# 2211B_SysArrosageAuto_MCU.net
KiCad netlist of a schematic drawn in Altium Designer
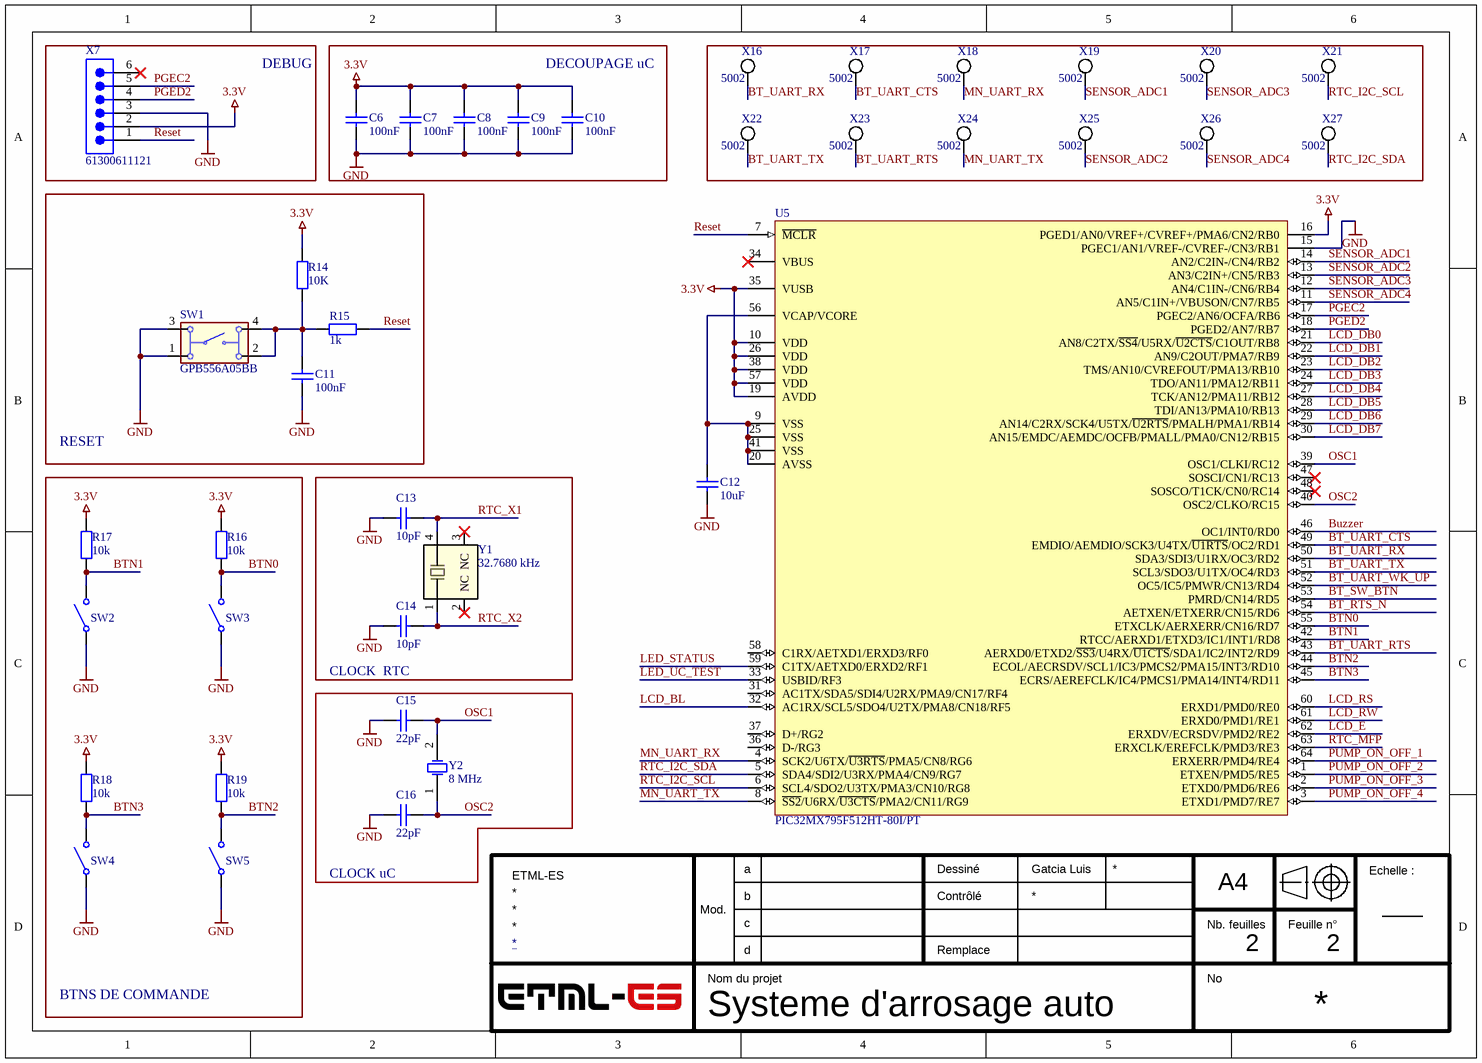
[diagram p0: 2211B_SysArrosageAuto_MCU.SchDoc]

(export (version "E")
  (design (tool "Eeschema 10.0.6"))
  (components
    (comp (ref "C6")
      (value "100nF")
      (footprint "CAPC2013X145X48NL20T23")
      (libsource (lib "Sys_Arossage") (part "Capacitor_Non-Polarized"))
    )
    (comp (ref "C7")
      (value "100nF")
      (footprint "CAPC2013X145X48NL20T23")
      (libsource (lib "Sys_Arossage") (part "Capacitor_Non-Polarized"))
    )
    (comp (ref "C8")
      (value "100nF")
      (footprint "CAPC2013X145X48NL20T23")
      (libsource (lib "Sys_Arossage") (part "Capacitor_Non-Polarized"))
    )
    (comp (ref "C9")
      (value "100nF")
      (footprint "CAPC2013X145X48NL20T23")
      (libsource (lib "Sys_Arossage") (part "Capacitor_Non-Polarized"))
    )
    (comp (ref "C10")
      (value "100nF")
      (footprint "CAPC2013X145X48NL20T23")
      (libsource (lib "Sys_Arossage") (part "Capacitor_Non-Polarized"))
    )
    (comp (ref "C11")
      (value "100nF")
      (footprint "CAPC2013X145X48NL20T23")
      (libsource (lib "Sys_Arossage") (part "Capacitor_Non-Polarized"))
    )
    (comp (ref "C12")
      (value "10uF")
      (footprint "CAPC2013X145X48NL20T23")
      (libsource (lib "Sys_Arossage") (part "Capacitor_Non-Polarized"))
    )
    (comp (ref "C13")
      (value "10pF")
      (footprint "CAPC2013X145X48NL20T23")
      (libsource (lib "Sys_Arossage") (part "Capacitor_Non-Polarized"))
    )
    (comp (ref "C14")
      (value "10pF")
      (footprint "CAPC2013X145X48NL20T23")
      (libsource (lib "Sys_Arossage") (part "Capacitor_Non-Polarized"))
    )
    (comp (ref "C15")
      (value "22pF")
      (footprint "CAPC2013X145X48NL20T23")
      (libsource (lib "Sys_Arossage") (part "Capacitor_Non-Polarized"))
    )
    (comp (ref "C16")
      (value "22pF")
      (footprint "CAPC2013X145X48NL20T23")
      (libsource (lib "Sys_Arossage") (part "Capacitor_Non-Polarized"))
    )
    (comp (ref "R14")
      (value "10K")
      (footprint "RC0805N_YAG-M")
      (description "SMD Chip Resistor, 10 kOhm, ± 1%, 125 mW, 0805 [2012 Metric], Thick Film, General Purpose")
      (fields
        (field (name "MANUFACTURER") "Yageo")
        (field (name "MANUFACTURER PART NUMBER") "RC0805FR-0710KL")
      )
      (libsource (lib "Sys_Arossage") (part "R-SMD"))
    )
    (comp (ref "R15")
      (value "1k")
      (footprint "RC0805N_YAG-M")
      (description "SMD Chip Resistor, 10 kOhm, ± 1%, 125 mW, 0805 [2012 Metric], Thick Film, General Purpose")
      (fields
        (field (name "MANUFACTURER") "Yageo")
        (field (name "MANUFACTURER PART NUMBER") "RC0805FR-0710KL")
      )
      (libsource (lib "") (part "R-SMD_1"))
    )
    (comp (ref "R16")
      (value "10k")
      (footprint "RC0805N_YAG-M")
      (description "SMD Chip Resistor, 10 kOhm, ± 1%, 125 mW, 0805 [2012 Metric], Thick Film, General Purpose")
      (fields
        (field (name "MANUFACTURER") "Yageo")
        (field (name "MANUFACTURER PART NUMBER") "RC0805FR-0710KL")
      )
      (libsource (lib "Sys_Arossage") (part "R-SMD"))
    )
    (comp (ref "R17")
      (value "10k")
      (footprint "RC0805N_YAG-M")
      (description "SMD Chip Resistor, 10 kOhm, ± 1%, 125 mW, 0805 [2012 Metric], Thick Film, General Purpose")
      (fields
        (field (name "MANUFACTURER") "Yageo")
        (field (name "MANUFACTURER PART NUMBER") "RC0805FR-0710KL")
      )
      (libsource (lib "Sys_Arossage") (part "R-SMD"))
    )
    (comp (ref "R18")
      (value "10k")
      (footprint "RC0805N_YAG-M")
      (description "SMD Chip Resistor, 10 kOhm, ± 1%, 125 mW, 0805 [2012 Metric], Thick Film, General Purpose")
      (fields
        (field (name "MANUFACTURER") "Yageo")
        (field (name "MANUFACTURER PART NUMBER") "RC0805FR-0710KL")
      )
      (libsource (lib "Sys_Arossage") (part "R-SMD"))
    )
    (comp (ref "R19")
      (value "10k")
      (footprint "RC0805N_YAG-M")
      (description "SMD Chip Resistor, 10 kOhm, ± 1%, 125 mW, 0805 [2012 Metric], Thick Film, General Purpose")
      (fields
        (field (name "MANUFACTURER") "Yageo")
        (field (name "MANUFACTURER PART NUMBER") "RC0805FR-0710KL")
      )
      (libsource (lib "Sys_Arossage") (part "R-SMD"))
    )
    (comp (ref "SW1") (value "GPB556A05BB") (libsource (lib "Sys_Arossage") (part "SWITCH_SPST-NO")))
    (comp (ref "SW2")
      (value "Single-Pole,Single-Throw Switch")
      (footprint "FP-RP8100B2M1CEBLKBLKNIL-MFG")
      (libsource (lib "Sys_Arossage") (part "SPST SW"))
    )
    (comp (ref "SW3")
      (value "Single-Pole,Single-Throw Switch")
      (footprint "FP-RP8100B2M1CEBLKBLKNIL-MFG")
      (libsource (lib "Sys_Arossage") (part "SPST SW"))
    )
    (comp (ref "SW4")
      (value "Single-Pole,Single-Throw Switch")
      (footprint "FP-RP8100B2M1CEBLKBLKNIL-MFG")
      (libsource (lib "Sys_Arossage") (part "SPST SW"))
    )
    (comp (ref "SW5")
      (value "Single-Pole,Single-Throw Switch")
      (footprint "FP-RP8100B2M1CEBLKBLKNIL-MFG")
      (libsource (lib "Sys_Arossage") (part "SPST SW"))
    )
    (comp (ref "U5")
      (value "PIC32MX795F512HT-80I/PT")
      (footprint "TQFP-PT64_L")
      (libsource (lib "Sys_Arossage") (part "CMP-0048-00048-2"))
    )
    (comp (ref "X7")
      (value "61300611121")
      (footprint "61300611121")
      (description "THT Vertical Pin Header WR-PHD, Pitch 2.54 mm, Single Row, 6 pins")
      (fields (field (name "MANUFACTURER") "Wurth Electronics"))
      (libsource (lib "Sys_Arossage") (part "CMP-1502-01068-2_1"))
    )
    (comp (ref "X16")
      (value "5002")
      (footprint "Keystone_5002")
      (description "TEST THT MINIATURE WT")
      (fields (field (name "MANUFACTURER") "Keystone"))
      (libsource (lib "ETML-ES") (part "TEST"))
    )
    (comp (ref "X17")
      (value "5002")
      (footprint "Keystone_5002")
      (description "TEST THT MINIATURE WT")
      (fields (field (name "MANUFACTURER") "Keystone"))
      (libsource (lib "ETML-ES") (part "TEST"))
    )
    (comp (ref "X18")
      (value "5002")
      (footprint "Keystone_5002")
      (description "TEST THT MINIATURE WT")
      (fields (field (name "MANUFACTURER") "Keystone"))
      (libsource (lib "ETML-ES") (part "TEST"))
    )
    (comp (ref "X19")
      (value "5002")
      (footprint "Keystone_5002")
      (description "TEST THT MINIATURE WT")
      (fields (field (name "MANUFACTURER") "Keystone"))
      (libsource (lib "ETML-ES") (part "TEST"))
    )
    (comp (ref "X20")
      (value "5002")
      (footprint "Keystone_5002")
      (description "TEST THT MINIATURE WT")
      (fields (field (name "MANUFACTURER") "Keystone"))
      (libsource (lib "ETML-ES") (part "TEST"))
    )
    (comp (ref "X21")
      (value "5002")
      (footprint "Keystone_5002")
      (description "TEST THT MINIATURE WT")
      (fields (field (name "MANUFACTURER") "Keystone"))
      (libsource (lib "ETML-ES") (part "TEST"))
    )
    (comp (ref "X22")
      (value "5002")
      (footprint "Keystone_5002")
      (description "TEST THT MINIATURE WT")
      (fields (field (name "MANUFACTURER") "Keystone"))
      (libsource (lib "ETML-ES") (part "TEST"))
    )
    (comp (ref "X23")
      (value "5002")
      (footprint "Keystone_5002")
      (description "TEST THT MINIATURE WT")
      (fields (field (name "MANUFACTURER") "Keystone"))
      (libsource (lib "ETML-ES") (part "TEST"))
    )
    (comp (ref "X24")
      (value "5002")
      (footprint "Keystone_5002")
      (description "TEST THT MINIATURE WT")
      (fields (field (name "MANUFACTURER") "Keystone"))
      (libsource (lib "ETML-ES") (part "TEST"))
    )
    (comp (ref "X25")
      (value "5002")
      (footprint "Keystone_5002")
      (description "TEST THT MINIATURE WT")
      (fields (field (name "MANUFACTURER") "Keystone"))
      (libsource (lib "ETML-ES") (part "TEST"))
    )
    (comp (ref "X26")
      (value "5002")
      (footprint "Keystone_5002")
      (description "TEST THT MINIATURE WT")
      (fields (field (name "MANUFACTURER") "Keystone"))
      (libsource (lib "ETML-ES") (part "TEST"))
    )
    (comp (ref "X27")
      (value "5002")
      (footprint "Keystone_5002")
      (description "TEST THT MINIATURE WT")
      (fields (field (name "MANUFACTURER") "Keystone"))
      (libsource (lib "ETML-ES") (part "TEST"))
    )
    (comp (ref "Y1")
      (value "32.7680 kHz")
      (footprint "SOJ_MC-306_EPS-M")
      (description "CRYSTAL 32.7680KHZ 12.5PF SMD")
      (fields
        (field (name "MANUFACTURER_PART_NUMBER") "MC-306 32.7680K-A3: ROHS")
        (field (name "MANUFACTURER") "Epson")
        (field (name "COPYRIGHT") "Copyright (C) 2024 Ultra Librarian. All rights reserved.")
      )
      (libsource (lib "Sys_Arossage") (part "MC-306 32.7680K-A3{colon} ROHS"))
    )
    (comp (ref "Y2")
      (value "8 MHz")
      (description "Crystal 8MHz ±30ppm (Tol) ±50ppm (Stability) 18pF FUND 60Ohm 2-Pin HC-49/US SM SMD T/R")
      (fields
        (field (name "MANUFACTURER") "CTS")
        (field (name "MANUFACTURER PART NUMBER") "ATS080BSM-1")
        (field (name "PUBLISHER") "Altium Limited")
      )
      (libsource (lib "Sys_Arossage") (part "XTAL"))
    )
  )
  (nets
    (net (code "1") (name "/BTN0") (class "Default")
      (node (ref "R16") (pin "1") (pinfunction "1_1") (pintype "passive"))
      (node (ref "SW3") (pin "2") (pinfunction "2_2") (pintype "passive"))
      (node (ref "U5") (pin "55") (pinfunction "ETXCLK/AERXERR/CN16/RD7_55") (pintype "bidirectional"))
    )
    (net (code "2") (name "/BTN1") (class "Default")
      (node (ref "R17") (pin "1") (pinfunction "1_1") (pintype "passive"))
      (node (ref "SW2") (pin "2") (pinfunction "2_2") (pintype "passive"))
      (node (ref "U5") (pin "42") (pinfunction "RTCC/AERXD1/ETXD3/IC1/INT1/RD8_42") (pintype "bidirectional"))
    )
    (net (code "3") (name "/BTN2") (class "Default")
      (node (ref "R19") (pin "1") (pinfunction "1_1") (pintype "passive"))
      (node (ref "SW5") (pin "2") (pinfunction "2_2") (pintype "passive"))
      (node (ref "U5") (pin "44") (pinfunction "ECOL/AECRSDV/SCL1/IC3/PMCS2/PMA15/INT3/RD10_44") (pintype "bidirectional"))
    )
    (net (code "4") (name "/BTN3") (class "Default")
      (node (ref "R18") (pin "1") (pinfunction "1_1") (pintype "passive"))
      (node (ref "SW4") (pin "2") (pinfunction "2_2") (pintype "passive"))
      (node (ref "U5") (pin "45") (pinfunction "ECRS/AEREFCLK/IC4/PMCS1/PMA14/INT4/RD11_45") (pintype "bidirectional"))
    )
    (net (code "5") (name "/BT_RTS_N") (class "Default")
      (node (ref "U5") (pin "54") (pinfunction "AETXEN/ETXERR/CN15/RD6_54") (pintype "bidirectional"))
    )
    (net (code "6") (name "/BT_SW_BTN") (class "Default")
      (node (ref "U5") (pin "53") (pinfunction "PMRD/CN14/RD5_53") (pintype "bidirectional"))
    )
    (net (code "7") (name "/BT_UART_CTS") (class "Default")
      (node (ref "U5") (pin "49") (pinfunction "EMDIO/AEMDIO/SCK3/U4TX/~{U1RTS}/OC2/RD1_49") (pintype "bidirectional"))
      (node (ref "X17") (pin "1") (pinfunction "TP_1") (pintype "passive"))
    )
    (net (code "8") (name "/BT_UART_RTS") (class "Default")
      (node (ref "U5") (pin "43") (pinfunction "AERXD0/ETXD2/~{SS3}/U4RX/~{U1CTS}/SDA1/IC2/INT2/RD9_43") (pintype "bidirectional"))
      (node (ref "X23") (pin "1") (pinfunction "TP_1") (pintype "passive"))
    )
    (net (code "9") (name "/BT_UART_RX") (class "Default")
      (node (ref "U5") (pin "50") (pinfunction "SDA3/SDI3/U1RX/OC3/RD2_50") (pintype "bidirectional"))
      (node (ref "X16") (pin "1") (pinfunction "TP_1") (pintype "passive"))
    )
    (net (code "10") (name "/BT_UART_TX") (class "Default")
      (node (ref "U5") (pin "51") (pinfunction "SCL3/SDO3/U1TX/OC4/RD3_51") (pintype "bidirectional"))
      (node (ref "X22") (pin "1") (pinfunction "TP_1") (pintype "passive"))
    )
    (net (code "11") (name "/BT_UART_WK_UP") (class "Default")
      (node (ref "U5") (pin "52") (pinfunction "OC5/IC5/PMWR/CN13/RD4_52") (pintype "bidirectional"))
    )
    (net (code "12") (name "/Buzzer") (class "Default")
      (node (ref "U5") (pin "46") (pinfunction "OC1/INT0/RD0_46") (pintype "bidirectional"))
    )
    (net (code "13") (name "/LCD_BL") (class "Default")
      (node (ref "U5") (pin "32") (pinfunction "AC1RX/SCL5/SDO4/U2TX/PMA8/CN18/RF5_32") (pintype "bidirectional"))
    )
    (net (code "14") (name "/LCD_DB0") (class "Default")
      (node (ref "U5") (pin "21") (pinfunction "AN8/C2TX/~{SS4}/U5RX/~{U2CTS}/C1OUT/RB8_21") (pintype "bidirectional"))
    )
    (net (code "15") (name "/LCD_DB1") (class "Default")
      (node (ref "U5") (pin "22") (pinfunction "AN9/C2OUT/PMA7/RB9_22") (pintype "bidirectional"))
    )
    (net (code "16") (name "/LCD_DB2") (class "Default")
      (node (ref "U5") (pin "23") (pinfunction "TMS/AN10/CVREFOUT/PMA13/RB10_23") (pintype "bidirectional"))
    )
    (net (code "17") (name "/LCD_DB3") (class "Default")
      (node (ref "U5") (pin "24") (pinfunction "TDO/AN11/PMA12/RB11_24") (pintype "bidirectional"))
    )
    (net (code "18") (name "/LCD_DB4") (class "Default")
      (node (ref "U5") (pin "27") (pinfunction "TCK/AN12/PMA11/RB12_27") (pintype "bidirectional"))
    )
    (net (code "19") (name "/LCD_DB5") (class "Default")
      (node (ref "U5") (pin "28") (pinfunction "TDI/AN13/PMA10/RB13_28") (pintype "bidirectional"))
    )
    (net (code "20") (name "/LCD_DB6") (class "Default")
      (node (ref "U5") (pin "29") (pinfunction "AN14/C2RX/SCK4/U5TX/~{U2RTS}/PMALH/PMA1/RB14_29") (pintype "bidirectional"))
    )
    (net (code "21") (name "/LCD_DB7") (class "Default")
      (node (ref "U5") (pin "30") (pinfunction "AN15/EMDC/AEMDC/OCFB/PMALL/PMA0/CN12/RB15_30") (pintype "bidirectional"))
    )
    (net (code "22") (name "/LCD_E") (class "Default")
      (node (ref "U5") (pin "62") (pinfunction "ERXDV/ECRSDV/PMD2/RE2_62") (pintype "bidirectional"))
    )
    (net (code "23") (name "/LCD_RS") (class "Default")
      (node (ref "U5") (pin "60") (pinfunction "ERXD1/PMD0/RE0_60") (pintype "bidirectional"))
    )
    (net (code "24") (name "/LCD_RW") (class "Default")
      (node (ref "U5") (pin "61") (pinfunction "ERXD0/PMD1/RE1_61") (pintype "bidirectional"))
    )
    (net (code "25") (name "/LED_STATUS") (class "Default")
      (node (ref "U5") (pin "59") (pinfunction "C1TX/AETXD0/ERXD2/RF1_59") (pintype "bidirectional"))
    )
    (net (code "26") (name "/LED_UC_TEST") (class "Default")
      (node (ref "U5") (pin "33") (pinfunction "USBID/RF3_33") (pintype "bidirectional"))
    )
    (net (code "27") (name "/MN_UART_RX") (class "Default")
      (node (ref "U5") (pin "4") (pinfunction "SCK2/U6TX/~{U3RTS}/PMA5/CN8/RG6_4") (pintype "bidirectional"))
      (node (ref "X18") (pin "1") (pinfunction "TP_1") (pintype "passive"))
    )
    (net (code "28") (name "/MN_UART_TX") (class "Default")
      (node (ref "U5") (pin "8") (pinfunction "~{SS2}/U6RX/~{U3CTS}/PMA2/CN11/RG9_8") (pintype "bidirectional"))
      (node (ref "X24") (pin "1") (pinfunction "TP_1") (pintype "passive"))
    )
    (net (code "29") (name "/OSC1") (class "Default")
      (node (ref "C15") (pin "2") (pinfunction "2_2") (pintype "passive"))
      (node (ref "U5") (pin "39") (pinfunction "OSC1/CLKI/RC12_39") (pintype "bidirectional"))
      (node (ref "Y2") (pin "2") (pinfunction "OSC2_2") (pintype "passive"))
    )
    (net (code "30") (name "/OSC2") (class "Default")
      (node (ref "C16") (pin "2") (pinfunction "2_2") (pintype "passive"))
      (node (ref "U5") (pin "40") (pinfunction "OSC2/CLKO/RC15_40") (pintype "bidirectional"))
      (node (ref "Y2") (pin "1") (pinfunction "OSC1_1") (pintype "passive"))
    )
    (net (code "31") (name "/PGEC2") (class "Default")
      (node (ref "U5") (pin "17") (pinfunction "PGEC2/AN6/OCFA/RB6_17") (pintype "bidirectional"))
      (node (ref "X7") (pin "5") (pinfunction "5_5") (pintype "passive"))
    )
    (net (code "32") (name "/PGED2") (class "Default")
      (node (ref "U5") (pin "18") (pinfunction "PGED2/AN7/RB7_18") (pintype "bidirectional"))
      (node (ref "X7") (pin "4") (pinfunction "4_4") (pintype "passive"))
    )
    (net (code "33") (name "/PUMP_ON_OFF_1") (class "Default")
      (node (ref "U5") (pin "64") (pinfunction "ERXERR/PMD4/RE4_64") (pintype "bidirectional"))
    )
    (net (code "34") (name "/PUMP_ON_OFF_2") (class "Default")
      (node (ref "U5") (pin "1") (pinfunction "ETXEN/PMD5/RE5_1") (pintype "bidirectional"))
    )
    (net (code "35") (name "/PUMP_ON_OFF_3") (class "Default")
      (node (ref "U5") (pin "2") (pinfunction "ETXD0/PMD6/RE6_2") (pintype "bidirectional"))
    )
    (net (code "36") (name "/PUMP_ON_OFF_4") (class "Default")
      (node (ref "U5") (pin "3") (pinfunction "ETXD1/PMD7/RE7_3") (pintype "bidirectional"))
    )
    (net (code "37") (name "/RTC_I2C_SCL") (class "Default")
      (node (ref "U5") (pin "6") (pinfunction "SCL4/SDO2/U3TX/PMA3/CN10/RG8_6") (pintype "bidirectional"))
      (node (ref "X21") (pin "1") (pinfunction "TP_1") (pintype "passive"))
    )
    (net (code "38") (name "/RTC_I2C_SDA") (class "Default")
      (node (ref "U5") (pin "5") (pinfunction "SDA4/SDI2/U3RX/PMA4/CN9/RG7_5") (pintype "bidirectional"))
      (node (ref "X27") (pin "1") (pinfunction "TP_1") (pintype "passive"))
    )
    (net (code "39") (name "/RTC_MFP") (class "Default")
      (node (ref "U5") (pin "63") (pinfunction "ERXCLK/EREFCLK/PMD3/RE3_63") (pintype "bidirectional"))
    )
    (net (code "40") (name "/RTC_X1") (class "Default")
      (node (ref "C13") (pin "2") (pinfunction "2_2") (pintype "passive"))
      (node (ref "Y1") (pin "4") (pinfunction "4_4") (pintype "passive"))
    )
    (net (code "41") (name "/RTC_X2") (class "Default")
      (node (ref "C14") (pin "2") (pinfunction "2_2") (pintype "passive"))
      (node (ref "Y1") (pin "1") (pinfunction "1_1") (pintype "passive"))
    )
    (net (code "42") (name "/Reset") (class "Default")
      (node (ref "R15") (pin "2") (pinfunction "2_2") (pintype "passive"))
      (node (ref "U5") (pin "7") (pinfunction "~{MCLR}_7") (pintype "input"))
      (node (ref "X7") (pin "1") (pinfunction "1_1") (pintype "passive"))
    )
    (net (code "43") (name "/SENSOR_ADC1") (class "Default")
      (node (ref "U5") (pin "14") (pinfunction "AN2/C2IN-/CN4/RB2_14") (pintype "bidirectional"))
      (node (ref "X19") (pin "1") (pinfunction "TP_1") (pintype "passive"))
    )
    (net (code "44") (name "/SENSOR_ADC2") (class "Default")
      (node (ref "U5") (pin "13") (pinfunction "AN3/C2IN+/CN5/RB3_13") (pintype "bidirectional"))
      (node (ref "X25") (pin "1") (pinfunction "TP_1") (pintype "passive"))
    )
    (net (code "45") (name "/SENSOR_ADC3") (class "Default")
      (node (ref "U5") (pin "12") (pinfunction "AN4/C1IN-/CN6/RB4_12") (pintype "bidirectional"))
      (node (ref "X20") (pin "1") (pinfunction "TP_1") (pintype "passive"))
    )
    (net (code "46") (name "/SENSOR_ADC4") (class "Default")
      (node (ref "U5") (pin "11") (pinfunction "AN5/C1IN+/VBUSON/CN7/RB5_11") (pintype "bidirectional"))
      (node (ref "X26") (pin "1") (pinfunction "TP_1") (pintype "passive"))
    )
    (net (code "47") (name "3.3V") (class "Default")
      (node (ref "C10") (pin "2") (pinfunction "2_2") (pintype "passive"))
      (node (ref "C6") (pin "2") (pinfunction "2_2") (pintype "passive"))
      (node (ref "C7") (pin "2") (pinfunction "2_2") (pintype "passive"))
      (node (ref "C8") (pin "2") (pinfunction "2_2") (pintype "passive"))
      (node (ref "C9") (pin "2") (pinfunction "2_2") (pintype "passive"))
      (node (ref "R14") (pin "2") (pinfunction "2_2") (pintype "passive"))
      (node (ref "R16") (pin "2") (pinfunction "2_2") (pintype "passive"))
      (node (ref "R17") (pin "2") (pinfunction "2_2") (pintype "passive"))
      (node (ref "R18") (pin "2") (pinfunction "2_2") (pintype "passive"))
      (node (ref "R19") (pin "2") (pinfunction "2_2") (pintype "passive"))
      (node (ref "U5") (pin "10") (pinfunction "VDD_10") (pintype "passive"))
      (node (ref "U5") (pin "16") (pinfunction "PGED1/AN0/VREF+/CVREF+/PMA6/CN2/RB0_16") (pintype "power_in"))
      (node (ref "U5") (pin "19") (pinfunction "AVDD_19") (pintype "passive"))
      (node (ref "U5") (pin "26") (pinfunction "VDD_26") (pintype "passive"))
      (node (ref "U5") (pin "35") (pinfunction "VUSB_35") (pintype "passive"))
      (node (ref "U5") (pin "38") (pinfunction "VDD_38") (pintype "passive"))
      (node (ref "U5") (pin "57") (pinfunction "VDD_57") (pintype "passive"))
      (node (ref "X7") (pin "2") (pinfunction "2_2") (pintype "passive"))
    )
    (net (code "48") (name "GND") (class "Default")
      (node (ref "C10") (pin "1") (pinfunction "1_1") (pintype "passive"))
      (node (ref "C11") (pin "1") (pinfunction "1_1") (pintype "passive"))
      (node (ref "C12") (pin "1") (pinfunction "1_1") (pintype "passive"))
      (node (ref "C13") (pin "1") (pinfunction "1_1") (pintype "passive"))
      (node (ref "C14") (pin "1") (pinfunction "1_1") (pintype "passive"))
      (node (ref "C15") (pin "1") (pinfunction "1_1") (pintype "passive"))
      (node (ref "C16") (pin "1") (pinfunction "1_1") (pintype "passive"))
      (node (ref "C6") (pin "1") (pinfunction "1_1") (pintype "passive"))
      (node (ref "C7") (pin "1") (pinfunction "1_1") (pintype "passive"))
      (node (ref "C8") (pin "1") (pinfunction "1_1") (pintype "passive"))
      (node (ref "C9") (pin "1") (pinfunction "1_1") (pintype "passive"))
      (node (ref "SW1") (pin "1") (pinfunction "1_1") (pintype "passive"))
      (node (ref "SW1") (pin "3") (pinfunction "3_3") (pintype "passive"))
      (node (ref "SW2") (pin "1") (pinfunction "1_1") (pintype "passive"))
      (node (ref "SW3") (pin "1") (pinfunction "1_1") (pintype "passive"))
      (node (ref "SW4") (pin "1") (pinfunction "1_1") (pintype "passive"))
      (node (ref "SW5") (pin "1") (pinfunction "1_1") (pintype "passive"))
      (node (ref "U5") (pin "15") (pinfunction "PGEC1/AN1/VREF-/CVREF-/CN3/RB1_15") (pintype "power_in"))
      (node (ref "X7") (pin "3") (pinfunction "3_3") (pintype "passive"))
    )
    (net (code "49") (name "Net-(C11-Pad2)") (class "Default")
      (node (ref "C11") (pin "2") (pinfunction "2_2") (pintype "passive"))
      (node (ref "R14") (pin "1") (pinfunction "1_1") (pintype "passive"))
      (node (ref "R15") (pin "1") (pinfunction "1_1") (pintype "passive"))
      (node (ref "SW1") (pin "2") (pinfunction "2_2") (pintype "passive"))
      (node (ref "SW1") (pin "4") (pinfunction "4_4") (pintype "passive"))
    )
    (net (code "50") (name "Net-(U5-AVSS)") (class "Default")
      (node (ref "C12") (pin "2") (pinfunction "2_2") (pintype "passive"))
      (node (ref "U5") (pin "20") (pinfunction "AVSS_20") (pintype "passive"))
      (node (ref "U5") (pin "25") (pinfunction "VSS_25") (pintype "passive"))
      (node (ref "U5") (pin "41") (pinfunction "VSS_41") (pintype "passive"))
      (node (ref "U5") (pin "56") (pinfunction "VCAP/VCORE_56") (pintype "passive"))
      (node (ref "U5") (pin "9") (pinfunction "VSS_9") (pintype "passive"))
    )
    (net (code "51") (name "unconnected-(U5-AC1TX{slash}SDA5{slash}SDI4{slash}U2RX{slash}PMA9{slash}CN17{slash}RF4-Pad31)") (class "Default")
      (node (ref "U5") (pin "31") (pinfunction "AC1TX/SDA5/SDI4/U2RX/PMA9/CN17/RF4_31") (pintype "bidirectional"))
    )
    (net (code "52") (name "unconnected-(U5-C1RX{slash}AETXD1{slash}ERXD3{slash}RF0-Pad58)") (class "Default")
      (node (ref "U5") (pin "58") (pinfunction "C1RX/AETXD1/ERXD3/RF0_58") (pintype "bidirectional"))
    )
    (net (code "53") (name "unconnected-(U5-D+{slash}RG2-Pad37)") (class "Default")
      (node (ref "U5") (pin "37") (pinfunction "D+/RG2_37") (pintype "bidirectional"))
    )
    (net (code "54") (name "unconnected-(U5-D-{slash}RG3-Pad36)") (class "Default")
      (node (ref "U5") (pin "36") (pinfunction "D-/RG3_36") (pintype "bidirectional"))
    )
    (net (code "55") (name "unconnected-(U5-SOSCI{slash}CN1{slash}RC13-Pad47)") (class "Default")
      (node (ref "U5") (pin "47") (pinfunction "SOSCI/CN1/RC13_47") (pintype "bidirectional+no_connect"))
    )
    (net (code "56") (name "unconnected-(U5-SOSCO{slash}T1CK{slash}CN0{slash}RC14-Pad48)") (class "Default")
      (node (ref "U5") (pin "48") (pinfunction "SOSCO/T1CK/CN0/RC14_48") (pintype "bidirectional+no_connect"))
    )
    (net (code "57") (name "unconnected-(U5-VBUS-Pad34)") (class "Default")
      (node (ref "U5") (pin "34") (pinfunction "VBUS_34") (pintype "passive+no_connect"))
    )
    (net (code "58") (name "unconnected-(X7-Pad6)") (class "Default")
      (node (ref "X7") (pin "6") (pinfunction "6_6") (pintype "passive+no_connect"))
    )
    (net (code "59") (name "unconnected-(Y1-NC-Pad2)") (class "Default")
      (node (ref "Y1") (pin "2") (pinfunction "NC_2") (pintype "passive+no_connect"))
    )
    (net (code "60") (name "unconnected-(Y1-NC-Pad3)") (class "Default")
      (node (ref "Y1") (pin "3") (pinfunction "NC_3") (pintype "passive+no_connect"))
    )
  )
)
